# GPS.net
KiCad netlist of a schematic drawn in Altium Designer
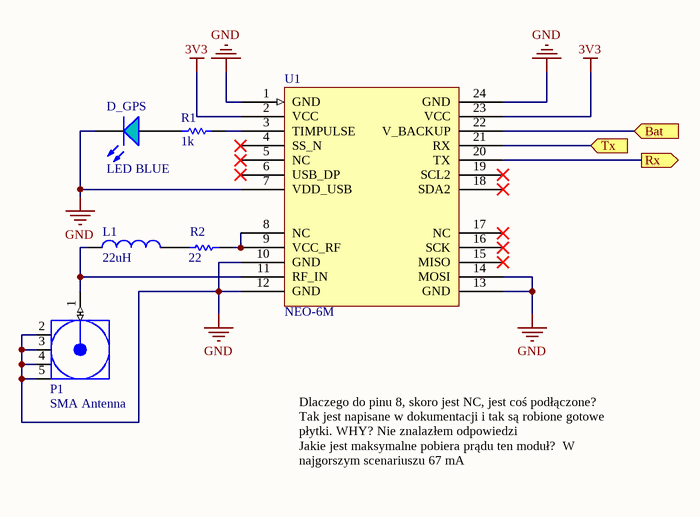
[diagram p0: GPS.SchDoc]

(export (version "E")
  (design (tool "Eeschema 10.0.6"))
  (components
    (comp (ref "D_GPS")
      (value "LED BLUE")
      (footprint "KPA_2106")
      (libsource (lib "agh_racing_2018") (part "LED BLUE"))
    )
    (comp (ref "L1")
      (value "22uH")
      (footprint "agh_racing_2018:IND_0603_IPC_HD")
      (description "Inductor")
      (fields (field (name "Comment") "Ind"))
      (libsource (lib "agh_racing_2018") (part "Ind"))
    )
    (comp (ref "P1")
      (value "SMA Antenna")
      (footprint "SMA_PCB_Female_Angle_connector")
      (description "Gniazdo; SMA; żeńskie; kątowe 90°; 50Ω; THT; na PCB; teflon; złocony")
      (libsource (lib "agh_racing_2018") (part "SMA PCB Female Antenna Angle connector"))
    )
    (comp (ref "R1")
      (value "1k")
      (footprint "agh_racing_2018:RES_0603_IPC_HD")
      (description "Resistor")
      (fields (field (name "Comment") "Res"))
      (libsource (lib "agh_racing_2018") (part "Res"))
    )
    (comp (ref "R2")
      (value "22")
      (footprint "agh_racing_2018:RES_0603_IPC_HD")
      (description "Resistor")
      (fields (field (name "Comment") "Res"))
      (libsource (lib "agh_racing_2018") (part "Res"))
    )
    (comp (ref "U1")
      (value "NEO-6M")
      (footprint "NEO-6M")
      (libsource (lib "agh_racing_2018") (part "NEO-6M"))
    )
  )
  (nets
    (net (code "1") (name "/Bat") (class "Default")
      (node (ref "U1") (pin "22") (pinfunction "V_BACKUP_22") (pintype "passive"))
    )
    (net (code "2") (name "/Rx") (class "Default")
      (node (ref "U1") (pin "20") (pinfunction "TX_20") (pintype "passive"))
    )
    (net (code "3") (name "/Tx") (class "Default")
      (node (ref "U1") (pin "21") (pinfunction "RX_21") (pintype "passive"))
    )
    (net (code "4") (name "3V3") (class "Default")
      (node (ref "U1") (pin "2") (pinfunction "VCC_2") (pintype "passive"))
      (node (ref "U1") (pin "23") (pinfunction "VCC_23") (pintype "passive"))
    )
    (net (code "5") (name "GND") (class "Default")
      (node (ref "D_GPS") (pin "2") (pinfunction "K_2") (pintype "passive"))
      (node (ref "P1") (pin "2") (pinfunction "GND_2") (pintype "power_in"))
      (node (ref "P1") (pin "3") (pinfunction "GND_3") (pintype "power_in"))
      (node (ref "P1") (pin "4") (pinfunction "GND_4") (pintype "power_in"))
      (node (ref "P1") (pin "5") (pinfunction "GND_5") (pintype "power_in"))
      (node (ref "U1") (pin "1") (pinfunction "GND_1") (pintype "input"))
      (node (ref "U1") (pin "10") (pinfunction "GND_10") (pintype "passive"))
      (node (ref "U1") (pin "12") (pinfunction "GND_12") (pintype "passive"))
      (node (ref "U1") (pin "13") (pinfunction "GND_13") (pintype "passive"))
      (node (ref "U1") (pin "14") (pinfunction "MOSI_14") (pintype "passive"))
      (node (ref "U1") (pin "24") (pinfunction "GND_24") (pintype "passive"))
      (node (ref "U1") (pin "7") (pinfunction "VDD_USB_7") (pintype "passive"))
    )
    (net (code "6") (name "Net-(D_GPS-A)") (class "Default")
      (node (ref "D_GPS") (pin "1") (pinfunction "A_1") (pintype "passive"))
      (node (ref "R1") (pin "1") (pinfunction "1_1") (pintype "passive"))
    )
    (net (code "7") (name "Net-(L1-Pad2)") (class "Default")
      (node (ref "L1") (pin "2") (pinfunction "2_2") (pintype "passive"))
      (node (ref "R2") (pin "1") (pinfunction "1_1") (pintype "passive"))
    )
    (net (code "8") (name "Net-(P1-Signal)") (class "Default")
      (node (ref "L1") (pin "1") (pinfunction "1_1") (pintype "passive"))
      (node (ref "P1") (pin "1") (pinfunction "Signal_1") (pintype "bidirectional"))
      (node (ref "U1") (pin "11") (pinfunction "RF_IN_11") (pintype "passive"))
    )
    (net (code "9") (name "Net-(U1-TIMPULSE)") (class "Default")
      (node (ref "R1") (pin "2") (pinfunction "2_2") (pintype "passive"))
      (node (ref "U1") (pin "3") (pinfunction "TIMPULSE_3") (pintype "passive"))
    )
    (net (code "10") (name "Net-(U1-VCC_RF)") (class "Default")
      (node (ref "R2") (pin "2") (pinfunction "2_2") (pintype "passive"))
      (node (ref "U1") (pin "8") (pinfunction "NC_8") (pintype "passive"))
      (node (ref "U1") (pin "9") (pinfunction "VCC_RF_9") (pintype "passive"))
    )
    (net (code "11") (name "unconnected-(U1-MISO-Pad15)") (class "Default")
      (node (ref "U1") (pin "15") (pinfunction "MISO_15") (pintype "passive+no_connect"))
    )
    (net (code "12") (name "unconnected-(U1-NC-Pad5)") (class "Default")
      (node (ref "U1") (pin "5") (pinfunction "NC_5") (pintype "passive+no_connect"))
    )
    (net (code "13") (name "unconnected-(U1-NC-Pad17)") (class "Default")
      (node (ref "U1") (pin "17") (pinfunction "NC_17") (pintype "passive+no_connect"))
    )
    (net (code "14") (name "unconnected-(U1-SCK-Pad16)") (class "Default")
      (node (ref "U1") (pin "16") (pinfunction "SCK_16") (pintype "passive+no_connect"))
    )
    (net (code "15") (name "unconnected-(U1-SCL2-Pad19)") (class "Default")
      (node (ref "U1") (pin "19") (pinfunction "SCL2_19") (pintype "passive+no_connect"))
    )
    (net (code "16") (name "unconnected-(U1-SDA2-Pad18)") (class "Default")
      (node (ref "U1") (pin "18") (pinfunction "SDA2_18") (pintype "passive+no_connect"))
    )
    (net (code "17") (name "unconnected-(U1-SS_N-Pad4)") (class "Default")
      (node (ref "U1") (pin "4") (pinfunction "SS_N_4") (pintype "passive+no_connect"))
    )
    (net (code "18") (name "unconnected-(U1-USB_DP-Pad6)") (class "Default")
      (node (ref "U1") (pin "6") (pinfunction "USB_DP_6") (pintype "passive+no_connect"))
    )
  )
)
